# Main_In.net
KiCad netlist of a schematic drawn in Altium Designer
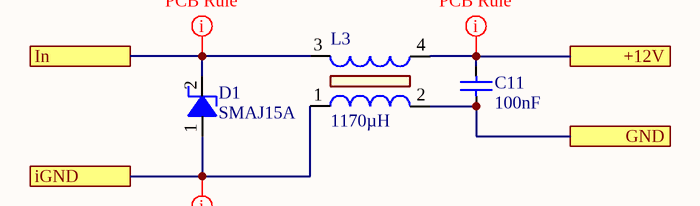
[diagram p0: Main_In.SchDoc]

(export (version "E")
  (design (tool "Eeschema 10.0.6"))
  (components
    (comp (ref "C11")
      (value "100nF")
      (footprint "C0603V")
      (description "MLCC, 0.1uF 16V 10% X7R 0603")
      (fields (field (name "PART NUMBER") "C0000005") (field (name "VOLTAGE") "16"))
      (libsource (lib "KTU_DB") (part "C_SM"))
    )
    (comp (ref "D1")
      (value "SMAJ15A")
      (footprint "DO-214AC")
      (description "DIODE, TVS, 15V, 400W")
      (fields (field (name "PART NUMBER") "D0000004") (field (name "MANUFACTURER") "MULTICOMP"))
      (libsource (lib "KTU_DB") (part "Diode_transzorb"))
    )
    (comp (ref "L3")
      (value "1170µH")
      (footprint "Polecat")
      (description "INDUCTOR COM MODE 1.17MH SMD")
      (fields (field (name "PART NUMBER") "L0000055") (field (name "MANUFACTURER") "PULSE Electronics"))
      (libsource (lib "KTU_DB") (part "L_common_mode"))
    )
  )
  (nets
    (net (code "1") (name "/+12V") (class "Default")
      (node (ref "C11") (pin "2") (pinfunction "2_2") (pintype "passive"))
      (node (ref "L3") (pin "4") (pinfunction "4_4") (pintype "passive"))
    )
    (net (code "2") (name "/GND") (class "Default")
      (node (ref "C11") (pin "1") (pinfunction "1_1") (pintype "passive"))
      (node (ref "L3") (pin "2") (pinfunction "2_2") (pintype "passive"))
    )
    (net (code "3") (name "/In") (class "Default")
      (node (ref "D1") (pin "2") (pinfunction "CATHODE_2") (pintype "passive"))
      (node (ref "L3") (pin "3") (pinfunction "3_3") (pintype "passive"))
    )
    (net (code "4") (name "/iGND") (class "Default")
      (node (ref "D1") (pin "1") (pinfunction "ANODE_1") (pintype "passive"))
      (node (ref "L3") (pin "1") (pinfunction "1_1") (pintype "passive"))
    )
  )
)
